# BpodFSM_r2_5.net
KiCad netlist of a schematic drawn in EAGLE
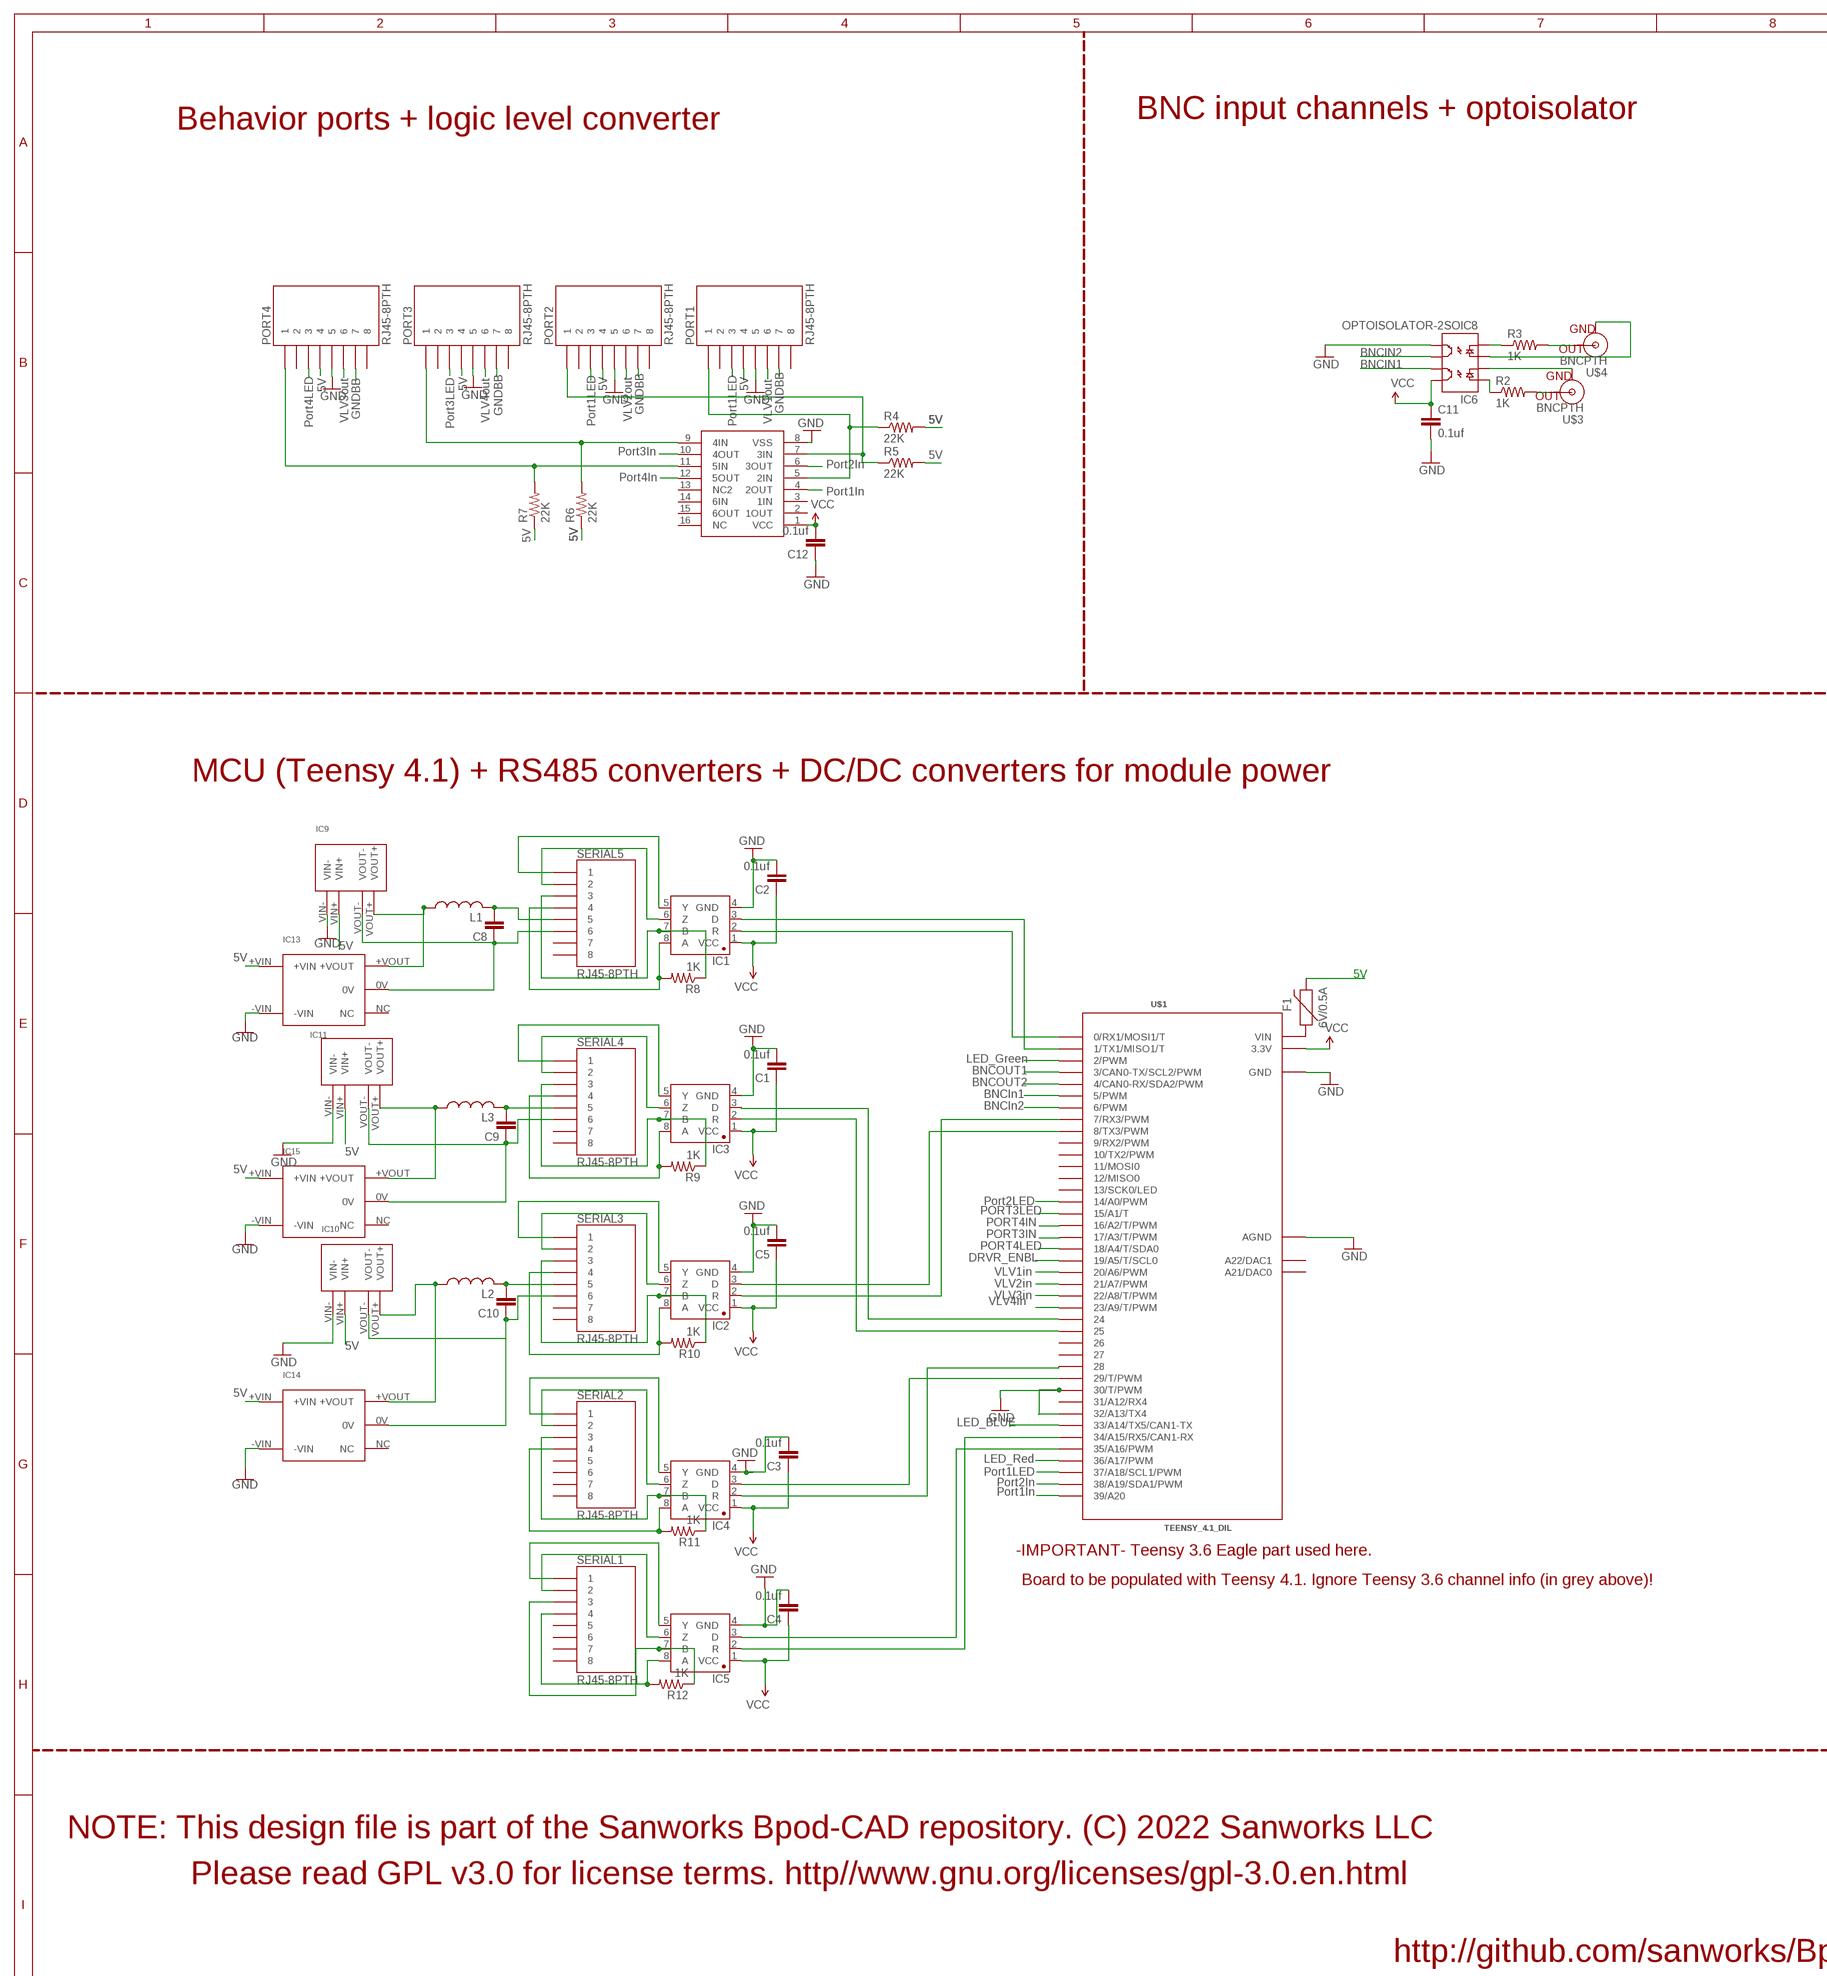
[diagram p0: schematic, sheet 1, part 1 of 2]
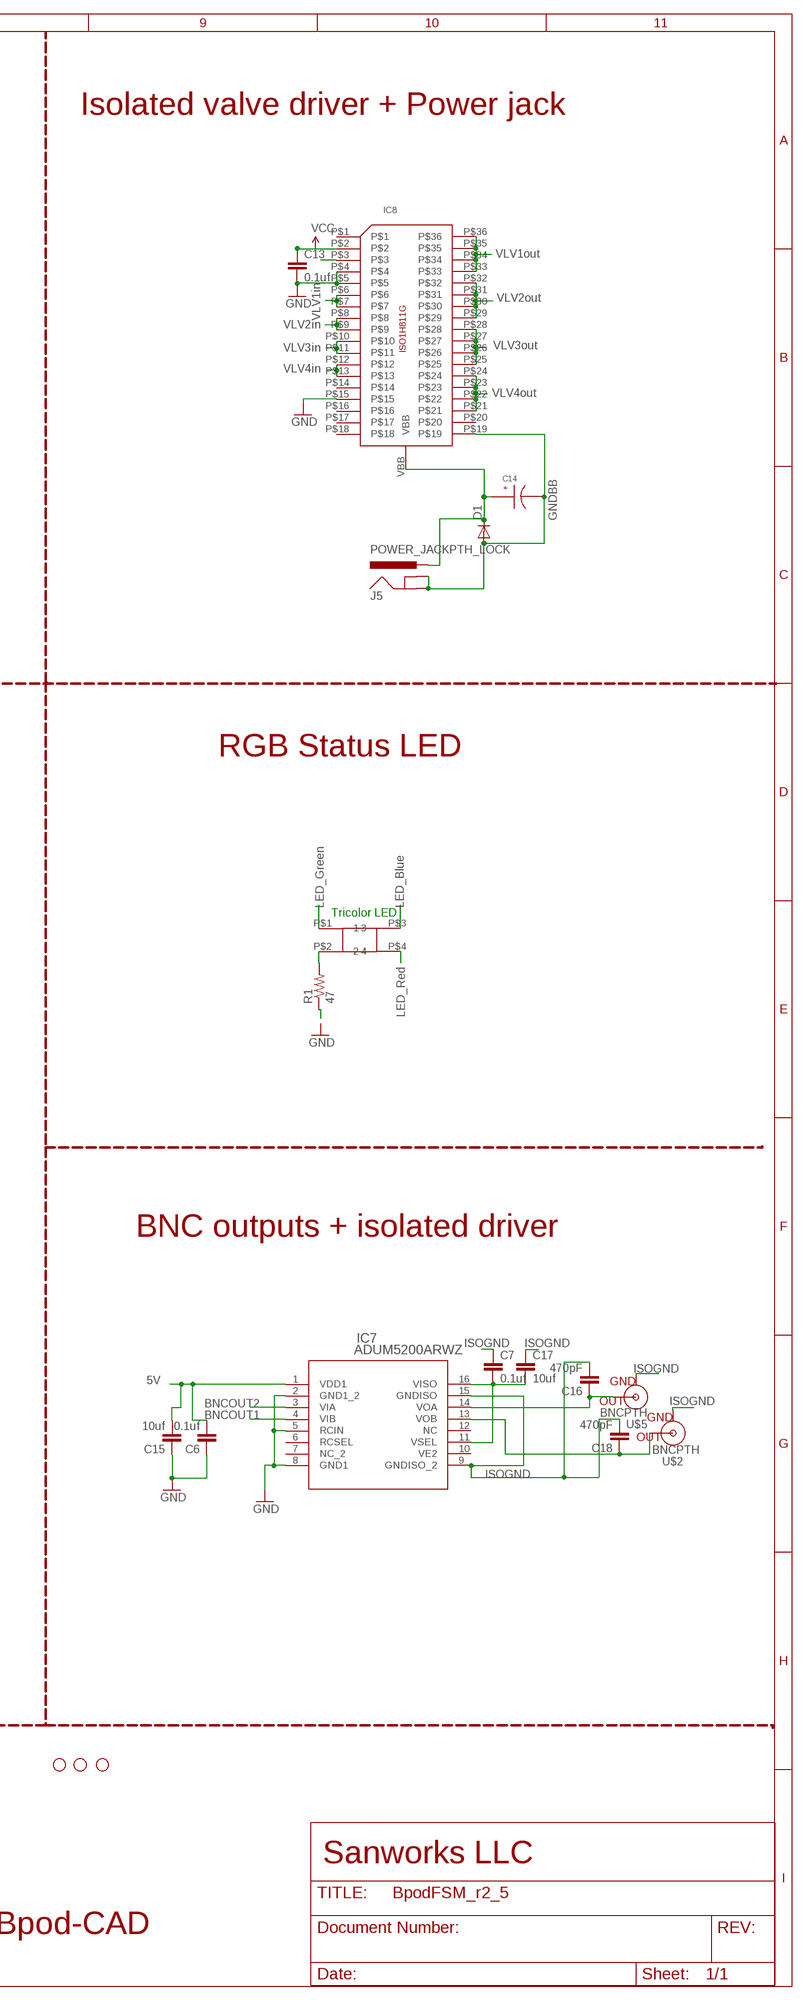
[diagram p1: schematic, sheet 1, part 2 of 2]

(export (version "E")
  (design (tool "Eeschema 10.0.6"))
  (components
    (comp (ref "C1")
      (value "0.1uf")
      (footprint "eagle-import:1206@1")
      (libsource (lib "eagle-import") (part "CAP1206"))
    )
    (comp (ref "C2")
      (value "0.1uf")
      (footprint "eagle-import:1206@1")
      (libsource (lib "eagle-import") (part "CAP1206"))
    )
    (comp (ref "C3")
      (value "0.1uf")
      (footprint "eagle-import:1206@1")
      (libsource (lib "eagle-import") (part "CAP1206"))
    )
    (comp (ref "C4")
      (value "0.1uf")
      (footprint "eagle-import:1206@1")
      (libsource (lib "eagle-import") (part "CAP1206"))
    )
    (comp (ref "C5")
      (value "0.1uf")
      (footprint "eagle-import:1206@1")
      (libsource (lib "eagle-import") (part "CAP1206"))
    )
    (comp (ref "C6")
      (value "0.1uf")
      (footprint "eagle-import:0805")
      (libsource (lib "eagle-import") (part "1.0UF-0805-25V-10%"))
    )
    (comp (ref "C7")
      (value "0.1uf")
      (footprint "eagle-import:0805")
      (libsource (lib "eagle-import") (part "1.0UF-0805-25V-10%"))
    )
    (comp (ref "C8")
      (value "CAP1206")
      (footprint "eagle-import:1206@1")
      (libsource (lib "eagle-import") (part "CAP1206"))
    )
    (comp (ref "C9")
      (value "CAP1206")
      (footprint "eagle-import:1206@1")
      (libsource (lib "eagle-import") (part "CAP1206"))
    )
    (comp (ref "C10")
      (value "CAP1206")
      (footprint "eagle-import:1206@1")
      (libsource (lib "eagle-import") (part "CAP1206"))
    )
    (comp (ref "C11")
      (value "0.1uf")
      (footprint "eagle-import:1206@1")
      (libsource (lib "eagle-import") (part "CAP1206"))
    )
    (comp (ref "C12")
      (value "0.1uf")
      (footprint "eagle-import:1206@1")
      (libsource (lib "eagle-import") (part "CAP1206"))
    )
    (comp (ref "C13")
      (value "0.1uf")
      (footprint "eagle-import:1206@1")
      (libsource (lib "eagle-import") (part "CAP1206"))
    )
    (comp (ref "C14")
      (value "EEE-FK1H100UR")
      (footprint "eagle-import:EEE-FK1H100UR")
      (libsource (lib "eagle-import") (part "EEE-FK1H100UR"))
    )
    (comp (ref "C15")
      (value "10uf")
      (footprint "eagle-import:1206@1")
      (libsource (lib "eagle-import") (part "CAP1206"))
    )
    (comp (ref "C16")
      (value "470pF")
      (footprint "eagle-import:0805")
      (libsource (lib "eagle-import") (part "1.0UF-0805-25V-10%"))
    )
    (comp (ref "C17")
      (value "10uf")
      (footprint "eagle-import:1206@1")
      (libsource (lib "eagle-import") (part "CAP1206"))
    )
    (comp (ref "C18")
      (value "470pF")
      (footprint "eagle-import:0805")
      (libsource (lib "eagle-import") (part "1.0UF-0805-25V-10%"))
    )
    (comp (ref "D1")
      (value "DIODE-DO214AA")
      (footprint "eagle-import:DO214AA")
      (libsource (lib "eagle-import") (part "DIODE-DO214AA"))
    )
    (comp (ref "F1")
      (value "6V/0.5A")
      (footprint "eagle-import:1206")
      (libsource (lib "eagle-import") (part "PPTC_HALF-AMP"))
    )
    (comp (ref "IC1")
      (value "SN65HVD31DR")
      (footprint "eagle-import:SO08")
      (libsource (lib "eagle-import") (part "SN65HVD31DR"))
    )
    (comp (ref "IC2")
      (value "SN65HVD31DR")
      (footprint "eagle-import:SO08")
      (libsource (lib "eagle-import") (part "SN65HVD31DR"))
    )
    (comp (ref "IC3")
      (value "SN65HVD31DR")
      (footprint "eagle-import:SO08")
      (libsource (lib "eagle-import") (part "SN65HVD31DR"))
    )
    (comp (ref "IC4")
      (value "SN65HVD31DR")
      (footprint "eagle-import:SO08")
      (libsource (lib "eagle-import") (part "SN65HVD31DR"))
    )
    (comp (ref "IC5")
      (value "SN65HVD31DR")
      (footprint "eagle-import:SO08")
      (libsource (lib "eagle-import") (part "SN65HVD31DR"))
    )
    (comp (ref "IC6")
      (value "OPTOISOLATOR-2SOIC8")
      (footprint "eagle-import:SO08-2")
      (libsource (lib "eagle-import") (part "OPTOISOLATOR-2SOIC8"))
    )
    (comp (ref "IC7")
      (value "ADUM5200ARWZ")
      (footprint "eagle-import:RW_16")
      (libsource (lib "eagle-import") (part "ADUM5200ARWZ"))
    )
    (comp (ref "IC8")
      (value "ISO1H811G")
      (footprint "eagle-import:ISO1H811G")
      (libsource (lib "eagle-import") (part "ISO1H811G"))
    )
    (comp (ref "IC9")
      (value "NME0509SC")
      (footprint "eagle-import:NME0509SC")
      (libsource (lib "eagle-import") (part "NME0509SC"))
    )
    (comp (ref "IC10")
      (value "NME0509SC")
      (footprint "eagle-import:NME0509SC")
      (libsource (lib "eagle-import") (part "NME0509SC"))
    )
    (comp (ref "IC11")
      (value "NME0509SC")
      (footprint "eagle-import:NME0509SC")
      (libsource (lib "eagle-import") (part "NME0509SC"))
    )
    (comp (ref "IC12")
      (value "CD4050")
      (footprint "eagle-import:SO16")
      (libsource (lib "eagle-import") (part "CD4050"))
    )
    (comp (ref "IC13")
      (value "MTU1D0505MC")
      (footprint "eagle-import:MTU1D0505MC")
      (libsource (lib "eagle-import") (part "MTU1D0505MC"))
    )
    (comp (ref "IC14")
      (value "MTU1D0505MC")
      (footprint "eagle-import:MTU1D0505MC")
      (libsource (lib "eagle-import") (part "MTU1D0505MC"))
    )
    (comp (ref "IC15")
      (value "MTU1D0505MC")
      (footprint "eagle-import:MTU1D0505MC")
      (libsource (lib "eagle-import") (part "MTU1D0505MC"))
    )
    (comp (ref "J5")
      (value "POWER_JACKPTH_LOCK")
      (footprint "eagle-import:POWER_JACK_PTH_LOCK")
      (libsource (lib "eagle-import") (part "POWER_JACKPTH_LOCK"))
    )
    (comp (ref "JP3")
      (value "STAND-OFF")
      (footprint "eagle-import:STAND-OFF")
      (libsource (lib "eagle-import") (part "STAND-OFF"))
    )
    (comp (ref "JP4")
      (value "STAND-OFF")
      (footprint "eagle-import:STAND-OFF")
      (libsource (lib "eagle-import") (part "STAND-OFF"))
    )
    (comp (ref "JP5")
      (value "STAND-OFF")
      (footprint "eagle-import:STAND-OFF")
      (libsource (lib "eagle-import") (part "STAND-OFF"))
    )
    (comp (ref "L1")
      (value "L-USL3225M")
      (footprint "eagle-import:L3225M")
      (libsource (lib "eagle-import") (part "L-USL3225M"))
    )
    (comp (ref "L2")
      (value "L-USL3225M")
      (footprint "eagle-import:L3225M")
      (libsource (lib "eagle-import") (part "L-USL3225M"))
    )
    (comp (ref "L3")
      (value "L-USL3225M")
      (footprint "eagle-import:L3225M")
      (libsource (lib "eagle-import") (part "L-USL3225M"))
    )
    (comp (ref "PORT1")
      (value "RJ45-8PTH")
      (footprint "eagle-import:RJ45-8")
      (libsource (lib "eagle-import") (part "RJ45-8PTH"))
    )
    (comp (ref "PORT2")
      (value "RJ45-8PTH")
      (footprint "eagle-import:RJ45-8")
      (libsource (lib "eagle-import") (part "RJ45-8PTH"))
    )
    (comp (ref "PORT3")
      (value "RJ45-8PTH")
      (footprint "eagle-import:RJ45-8")
      (libsource (lib "eagle-import") (part "RJ45-8PTH"))
    )
    (comp (ref "PORT4")
      (value "RJ45-8PTH")
      (footprint "eagle-import:RJ45-8")
      (libsource (lib "eagle-import") (part "RJ45-8PTH"))
    )
    (comp (ref "R1")
      (value "47")
      (footprint "eagle-import:1206")
      (libsource (lib "eagle-import") (part "RESISTOR1206"))
    )
    (comp (ref "R2")
      (value "1K")
      (footprint "eagle-import:1206")
      (libsource (lib "eagle-import") (part "SparkFun-Resistors_RESISTOR1206"))
    )
    (comp (ref "R3")
      (value "1K")
      (footprint "eagle-import:1206")
      (libsource (lib "eagle-import") (part "SparkFun-Resistors_RESISTOR1206"))
    )
    (comp (ref "R4")
      (value "22K")
      (footprint "eagle-import:1206")
      (libsource (lib "eagle-import") (part "SparkFun-Resistors_RESISTOR1206"))
    )
    (comp (ref "R5")
      (value "22K")
      (footprint "eagle-import:1206")
      (libsource (lib "eagle-import") (part "SparkFun-Resistors_RESISTOR1206"))
    )
    (comp (ref "R6")
      (value "22K")
      (footprint "eagle-import:1206")
      (libsource (lib "eagle-import") (part "SparkFun-Resistors_RESISTOR1206"))
    )
    (comp (ref "R7")
      (value "22K")
      (footprint "eagle-import:1206")
      (libsource (lib "eagle-import") (part "SparkFun-Resistors_RESISTOR1206"))
    )
    (comp (ref "R8")
      (value "1K")
      (footprint "eagle-import:1206")
      (libsource (lib "eagle-import") (part "SparkFun-Resistors_RESISTOR1206"))
    )
    (comp (ref "R9")
      (value "1K")
      (footprint "eagle-import:1206")
      (libsource (lib "eagle-import") (part "SparkFun-Resistors_RESISTOR1206"))
    )
    (comp (ref "R10")
      (value "1K")
      (footprint "eagle-import:1206")
      (libsource (lib "eagle-import") (part "SparkFun-Resistors_RESISTOR1206"))
    )
    (comp (ref "R11")
      (value "1K")
      (footprint "eagle-import:1206")
      (libsource (lib "eagle-import") (part "SparkFun-Resistors_RESISTOR1206"))
    )
    (comp (ref "R12")
      (value "1K")
      (footprint "eagle-import:1206")
      (libsource (lib "eagle-import") (part "SparkFun-Resistors_RESISTOR1206"))
    )
    (comp (ref "SERIAL1")
      (value "RJ45-8PTH")
      (footprint "eagle-import:RJ45-8")
      (libsource (lib "eagle-import") (part "RJ45-8PTH"))
    )
    (comp (ref "SERIAL2")
      (value "RJ45-8PTH")
      (footprint "eagle-import:RJ45-8")
      (libsource (lib "eagle-import") (part "RJ45-8PTH"))
    )
    (comp (ref "SERIAL3")
      (value "RJ45-8PTH")
      (footprint "eagle-import:RJ45-8")
      (libsource (lib "eagle-import") (part "RJ45-8PTH"))
    )
    (comp (ref "SERIAL4")
      (value "RJ45-8PTH")
      (footprint "eagle-import:RJ45-8")
      (libsource (lib "eagle-import") (part "RJ45-8PTH"))
    )
    (comp (ref "SERIAL5")
      (value "RJ45-8PTH")
      (footprint "eagle-import:RJ45-8")
      (libsource (lib "eagle-import") (part "RJ45-8PTH"))
    )
    (comp (ref "U$1")
      (value "TEENSY_4.1_DIL")
      (footprint "eagle-import:TEENSY_3.6_DIL")
      (libsource (lib "eagle-import") (part "TEENSY_3.6_DIL"))
    )
    (comp (ref "U$2")
      (value "BNCPTH")
      (footprint "eagle-import:BNC")
      (libsource (lib "eagle-import") (part "BNCPTH"))
    )
    (comp (ref "U$3")
      (value "BNCPTH")
      (footprint "eagle-import:BNC")
      (libsource (lib "eagle-import") (part "BNCPTH"))
    )
    (comp (ref "U$4")
      (value "BNCPTH")
      (footprint "eagle-import:BNC")
      (libsource (lib "eagle-import") (part "BNCPTH"))
    )
    (comp (ref "U$5")
      (value "BNCPTH")
      (footprint "eagle-import:BNC")
      (libsource (lib "eagle-import") (part "BNCPTH"))
    )
    (comp (ref "U$8")
      (value "SQUARE_TRICOLOR_LED")
      (footprint "eagle-import:SQUARE_TRICOLOR_LED")
      (libsource (lib "eagle-import") (part "SQUARE_TRICOLOR_LED"))
    )
  )
  (nets
    (net (code "1") (name "/5V") (class "Default")
      (node (ref "C15") (pin "2") (pinfunction "2_2") (pintype "passive"))
      (node (ref "C6") (pin "2") (pinfunction "2_2") (pintype "passive"))
      (node (ref "F1") (pin "2") (pinfunction "2_2") (pintype "bidirectional"))
      (node (ref "IC10") (pin "VIN+") (pinfunction "VIN+_VIN+") (pintype "bidirectional"))
      (node (ref "IC11") (pin "VIN+") (pinfunction "VIN+_VIN+") (pintype "bidirectional"))
      (node (ref "IC13") (pin "+VIN") (pinfunction "+VIN_+VIN") (pintype "bidirectional"))
      (node (ref "IC14") (pin "+VIN") (pinfunction "+VIN_+VIN") (pintype "bidirectional"))
      (node (ref "IC15") (pin "+VIN") (pinfunction "+VIN_+VIN") (pintype "bidirectional"))
      (node (ref "IC7") (pin "1") (pinfunction "VDD1_1") (pintype "passive"))
      (node (ref "IC9") (pin "VIN+") (pinfunction "VIN+_VIN+") (pintype "bidirectional"))
      (node (ref "PORT1") (pin "4") (pinfunction "4_4") (pintype "bidirectional"))
      (node (ref "PORT2") (pin "4") (pinfunction "4_4") (pintype "bidirectional"))
      (node (ref "PORT3") (pin "4") (pinfunction "4_4") (pintype "bidirectional"))
      (node (ref "PORT4") (pin "4") (pinfunction "4_4") (pintype "bidirectional"))
      (node (ref "R4") (pin "2") (pinfunction "2_2") (pintype "passive"))
      (node (ref "R5") (pin "2") (pinfunction "2_2") (pintype "passive"))
      (node (ref "R6") (pin "1") (pinfunction "1_1") (pintype "passive"))
      (node (ref "R7") (pin "1") (pinfunction "1_1") (pintype "passive"))
    )
    (net (code "2") (name "/BNCIN1") (class "Default")
      (node (ref "IC6") (pin "7") (pinfunction "EM1_7") (pintype "bidirectional"))
      (node (ref "U$1") (pin "6") (pinfunction "6/PWM_6") (pintype "bidirectional"))
    )
    (net (code "3") (name "/BNCIN2") (class "Default")
      (node (ref "IC6") (pin "6") (pinfunction "CL2_6") (pintype "bidirectional"))
      (node (ref "U$1") (pin "5") (pinfunction "5/PWM_5") (pintype "bidirectional"))
    )
    (net (code "4") (name "/BNCOUT1") (class "Default")
      (node (ref "IC7") (pin "4") (pinfunction "VIB_4") (pintype "passive"))
      (node (ref "U$1") (pin "4") (pinfunction "4/CAN0-RX/SDA2/PWM_4") (pintype "bidirectional"))
    )
    (net (code "5") (name "/BNCOUT2") (class "Default")
      (node (ref "IC7") (pin "3") (pinfunction "VIA_3") (pintype "passive"))
      (node (ref "U$1") (pin "3") (pinfunction "3/CAN0-TX/SCL2/PWM_3") (pintype "bidirectional"))
    )
    (net (code "6") (name "/DRVR_ENBL") (class "Default")
      (node (ref "IC8") (pin "P$3") (pinfunction "P$3_P$3") (pintype "bidirectional"))
      (node (ref "U$1") (pin "19/A5") (pinfunction "19/A5/T/SCL0_19/A5") (pintype "bidirectional"))
    )
    (net (code "7") (name "/GNDBB") (class "Default")
      (node (ref "C14") (pin "CATHODE") (pinfunction "CATHODE_CATHODE") (pintype "bidirectional"))
      (node (ref "D1") (pin "A") (pinfunction "A_A") (pintype "passive"))
      (node (ref "IC8") (pin "P$19") (pinfunction "P$19_P$19") (pintype "bidirectional"))
      (node (ref "J5") (pin "GND") (pinfunction "GND_GND") (pintype "bidirectional"))
      (node (ref "J5") (pin "GNDBREAK") (pinfunction "GNDBREAK_GNDBREAK") (pintype "bidirectional"))
      (node (ref "PORT1") (pin "7") (pinfunction "7_7") (pintype "bidirectional"))
      (node (ref "PORT2") (pin "7") (pinfunction "7_7") (pintype "bidirectional"))
      (node (ref "PORT3") (pin "7") (pinfunction "7_7") (pintype "bidirectional"))
      (node (ref "PORT4") (pin "7") (pinfunction "7_7") (pintype "bidirectional"))
    )
    (net (code "8") (name "/ISOGND") (class "Default")
      (node (ref "C16") (pin "2") (pinfunction "2_2") (pintype "passive"))
      (node (ref "C17") (pin "1") (pinfunction "1_1") (pintype "passive"))
      (node (ref "C18") (pin "2") (pinfunction "2_2") (pintype "passive"))
      (node (ref "C7") (pin "1") (pinfunction "1_1") (pintype "passive"))
      (node (ref "IC7") (pin "15") (pinfunction "GNDISO_15") (pintype "passive"))
      (node (ref "IC7") (pin "9") (pinfunction "GNDISO_2_9") (pintype "passive"))
      (node (ref "U$2") (pin "GND") (pinfunction "GND_GND") (pintype "bidirectional"))
      (node (ref "U$5") (pin "GND") (pinfunction "GND_GND") (pintype "bidirectional"))
    )
    (net (code "9") (name "/LED_BLUE") (class "Default")
      (node (ref "U$1") (pin "33/A14") (pinfunction "33/A14/TX5/CAN1-TX_33/A14") (pintype "bidirectional"))
      (node (ref "U$8") (pin "P$3") (pinfunction "3_P$3") (pintype "bidirectional"))
    )
    (net (code "10") (name "/LED_GREEN") (class "Default")
      (node (ref "U$1") (pin "2") (pinfunction "2/PWM_2") (pintype "bidirectional"))
      (node (ref "U$8") (pin "P$1") (pinfunction "1_P$1") (pintype "bidirectional"))
    )
    (net (code "11") (name "/LED_RED") (class "Default")
      (node (ref "U$1") (pin "36/A17") (pinfunction "36/A17/PWM_36/A17") (pintype "bidirectional"))
      (node (ref "U$8") (pin "P$4") (pinfunction "4_P$4") (pintype "bidirectional"))
    )
    (net (code "12") (name "/PORT1IN") (class "Default")
      (node (ref "IC12") (pin "4") (pinfunction "2OUT_4") (pintype "bidirectional"))
      (node (ref "U$1") (pin "39/A20") (pinfunction "39/A20_39/A20") (pintype "bidirectional"))
    )
    (net (code "13") (name "/PORT1LED") (class "Default")
      (node (ref "PORT1") (pin "3") (pinfunction "3_3") (pintype "bidirectional"))
      (node (ref "U$1") (pin "37/A18") (pinfunction "37/A18/SCL1/PWM_37/A18") (pintype "bidirectional"))
    )
    (net (code "14") (name "/PORT2IN") (class "Default")
      (node (ref "IC12") (pin "6") (pinfunction "3OUT_6") (pintype "bidirectional"))
      (node (ref "U$1") (pin "38/A19") (pinfunction "38/A19/SDA1/PWM_38/A19") (pintype "bidirectional"))
    )
    (net (code "15") (name "/PORT2LED") (class "Default")
      (node (ref "PORT2") (pin "3") (pinfunction "3_3") (pintype "bidirectional"))
      (node (ref "U$1") (pin "14/A0") (pinfunction "14/A0/PWM_14/A0") (pintype "bidirectional"))
    )
    (net (code "16") (name "/PORT3IN") (class "Default")
      (node (ref "IC12") (pin "10") (pinfunction "4OUT_10") (pintype "bidirectional"))
      (node (ref "U$1") (pin "17/A3") (pinfunction "17/A3/T/PWM_17/A3") (pintype "bidirectional"))
    )
    (net (code "17") (name "/PORT3LED") (class "Default")
      (node (ref "PORT3") (pin "3") (pinfunction "3_3") (pintype "bidirectional"))
      (node (ref "U$1") (pin "15/A1") (pinfunction "15/A1/T_15/A1") (pintype "bidirectional"))
    )
    (net (code "18") (name "/PORT4IN") (class "Default")
      (node (ref "IC12") (pin "12") (pinfunction "5OUT_12") (pintype "bidirectional"))
      (node (ref "U$1") (pin "16/A2") (pinfunction "16/A2/T/PWM_16/A2") (pintype "bidirectional"))
    )
    (net (code "19") (name "/PORT4LED") (class "Default")
      (node (ref "PORT4") (pin "3") (pinfunction "3_3") (pintype "bidirectional"))
      (node (ref "U$1") (pin "18/A4") (pinfunction "18/A4/T/SDA0_18/A4") (pintype "bidirectional"))
    )
    (net (code "20") (name "/VLV1IN") (class "Default")
      (node (ref "IC8") (pin "P$6") (pinfunction "P$6_P$6") (pintype "bidirectional"))
      (node (ref "IC8") (pin "P$7") (pinfunction "P$7_P$7") (pintype "bidirectional"))
      (node (ref "U$1") (pin "23/A9") (pinfunction "23/A9/T/PWM_23/A9") (pintype "bidirectional"))
    )
    (net (code "21") (name "/VLV1OUT") (class "Default")
      (node (ref "IC8") (pin "P$33") (pinfunction "P$33_P$33") (pintype "bidirectional"))
      (node (ref "IC8") (pin "P$34") (pinfunction "P$34_P$34") (pintype "bidirectional"))
      (node (ref "IC8") (pin "P$35") (pinfunction "P$35_P$35") (pintype "bidirectional"))
      (node (ref "IC8") (pin "P$36") (pinfunction "P$36_P$36") (pintype "bidirectional"))
      (node (ref "PORT1") (pin "6") (pinfunction "6_6") (pintype "bidirectional"))
    )
    (net (code "22") (name "/VLV2IN") (class "Default")
      (node (ref "IC8") (pin "P$8") (pinfunction "P$8_P$8") (pintype "bidirectional"))
      (node (ref "IC8") (pin "P$9") (pinfunction "P$9_P$9") (pintype "bidirectional"))
      (node (ref "U$1") (pin "22/A8") (pinfunction "22/A8/T/PWM_22/A8") (pintype "bidirectional"))
    )
    (net (code "23") (name "/VLV2OUT") (class "Default")
      (node (ref "IC8") (pin "P$29") (pinfunction "P$29_P$29") (pintype "bidirectional"))
      (node (ref "IC8") (pin "P$30") (pinfunction "P$30_P$30") (pintype "bidirectional"))
      (node (ref "IC8") (pin "P$31") (pinfunction "P$31_P$31") (pintype "bidirectional"))
      (node (ref "IC8") (pin "P$32") (pinfunction "P$32_P$32") (pintype "bidirectional"))
      (node (ref "PORT2") (pin "6") (pinfunction "6_6") (pintype "bidirectional"))
    )
    (net (code "24") (name "/VLV3IN") (class "Default")
      (node (ref "IC8") (pin "P$12") (pinfunction "P$12_P$12") (pintype "bidirectional"))
      (node (ref "IC8") (pin "P$13") (pinfunction "P$13_P$13") (pintype "bidirectional"))
      (node (ref "U$1") (pin "20/A6") (pinfunction "20/A6/PWM_20/A6") (pintype "bidirectional"))
    )
    (net (code "25") (name "/VLV3OUT") (class "Default")
      (node (ref "IC8") (pin "P$21") (pinfunction "P$21_P$21") (pintype "bidirectional"))
      (node (ref "IC8") (pin "P$22") (pinfunction "P$22_P$22") (pintype "bidirectional"))
      (node (ref "IC8") (pin "P$23") (pinfunction "P$23_P$23") (pintype "bidirectional"))
      (node (ref "IC8") (pin "P$24") (pinfunction "P$24_P$24") (pintype "bidirectional"))
      (node (ref "PORT3") (pin "6") (pinfunction "6_6") (pintype "bidirectional"))
    )
    (net (code "26") (name "/VLV4IN") (class "Default")
      (node (ref "IC8") (pin "P$10") (pinfunction "P$10_P$10") (pintype "bidirectional"))
      (node (ref "IC8") (pin "P$11") (pinfunction "P$11_P$11") (pintype "bidirectional"))
      (node (ref "U$1") (pin "21/A7") (pinfunction "21/A7/PWM_21/A7") (pintype "bidirectional"))
    )
    (net (code "27") (name "/VLV4OUT") (class "Default")
      (node (ref "IC8") (pin "P$25") (pinfunction "P$25_P$25") (pintype "bidirectional"))
      (node (ref "IC8") (pin "P$26") (pinfunction "P$26_P$26") (pintype "bidirectional"))
      (node (ref "IC8") (pin "P$27") (pinfunction "P$27_P$27") (pintype "bidirectional"))
      (node (ref "IC8") (pin "P$28") (pinfunction "P$28_P$28") (pintype "bidirectional"))
      (node (ref "PORT4") (pin "6") (pinfunction "6_6") (pintype "bidirectional"))
    )
    (net (code "28") (name "GND") (class "Default")
      (node (ref "C1") (pin "2") (pinfunction "2_2") (pintype "passive"))
      (node (ref "C11") (pin "2") (pinfunction "2_2") (pintype "passive"))
      (node (ref "C12") (pin "1") (pinfunction "1_1") (pintype "passive"))
      (node (ref "C13") (pin "2") (pinfunction "2_2") (pintype "passive"))
      (node (ref "C15") (pin "1") (pinfunction "1_1") (pintype "passive"))
      (node (ref "C2") (pin "2") (pinfunction "2_2") (pintype "passive"))
      (node (ref "C3") (pin "2") (pinfunction "2_2") (pintype "passive"))
      (node (ref "C4") (pin "2") (pinfunction "2_2") (pintype "passive"))
      (node (ref "C5") (pin "2") (pinfunction "2_2") (pintype "passive"))
      (node (ref "C6") (pin "1") (pinfunction "1_1") (pintype "passive"))
      (node (ref "IC1") (pin "4") (pinfunction "GND_4") (pintype "bidirectional"))
      (node (ref "IC10") (pin "VIN-") (pinfunction "VIN-_VIN-") (pintype "bidirectional"))
      (node (ref "IC11") (pin "VIN-") (pinfunction "VIN-_VIN-") (pintype "bidirectional"))
      (node (ref "IC12") (pin "8") (pinfunction "VSS_8") (pintype "bidirectional"))
      (node (ref "IC13") (pin "-VIN") (pinfunction "-VIN_-VIN") (pintype "bidirectional"))
      (node (ref "IC14") (pin "-VIN") (pinfunction "-VIN_-VIN") (pintype "bidirectional"))
      (node (ref "IC15") (pin "-VIN") (pinfunction "-VIN_-VIN") (pintype "bidirectional"))
      (node (ref "IC2") (pin "4") (pinfunction "GND_4") (pintype "bidirectional"))
      (node (ref "IC3") (pin "4") (pinfunction "GND_4") (pintype "bidirectional"))
      (node (ref "IC4") (pin "4") (pinfunction "GND_4") (pintype "bidirectional"))
      (node (ref "IC5") (pin "4") (pinfunction "GND_4") (pintype "bidirectional"))
      (node (ref "IC6") (pin "5") (pinfunction "EM2_5") (pintype "bidirectional"))
      (node (ref "IC7") (pin "2") (pinfunction "GND1_2_2") (pintype "passive"))
      (node (ref "IC7") (pin "5") (pinfunction "RCIN_5") (pintype "passive"))
      (node (ref "IC7") (pin "8") (pinfunction "GND1_8") (pintype "passive"))
      (node (ref "IC8") (pin "P$15") (pinfunction "P$15_P$15") (pintype "bidirectional"))
      (node (ref "IC8") (pin "P$4") (pinfunction "P$4_P$4") (pintype "bidirectional"))
      (node (ref "IC8") (pin "P$5") (pinfunction "P$5_P$5") (pintype "bidirectional"))
      (node (ref "IC9") (pin "VIN-") (pinfunction "VIN-_VIN-") (pintype "bidirectional"))
      (node (ref "PORT1") (pin "5") (pinfunction "5_5") (pintype "bidirectional"))
      (node (ref "PORT2") (pin "5") (pinfunction "5_5") (pintype "bidirectional"))
      (node (ref "PORT3") (pin "5") (pinfunction "5_5") (pintype "bidirectional"))
      (node (ref "PORT4") (pin "5") (pinfunction "5_5") (pintype "bidirectional"))
      (node (ref "R1") (pin "1") (pinfunction "1_1") (pintype "passive"))
      (node (ref "U$1") (pin "30") (pinfunction "30/T/PWM_30") (pintype "bidirectional"))
      (node (ref "U$1") (pin "32/A13") (pinfunction "32/A13/TX4_32/A13") (pintype "bidirectional"))
      (node (ref "U$1") (pin "AGND") (pinfunction "AGND_AGND") (pintype "power_in"))
      (node (ref "U$1") (pin "GND") (pinfunction "GND_GND") (pintype "power_in"))
      (node (ref "U$1") (pin "GND1") (pinfunction "GND_GND1") (pintype "power_in"))
    )
    (net (code "29") (name "Net-(C8-Pad1)") (class "Default")
      (node (ref "C8") (pin "1") (pinfunction "1_1") (pintype "passive"))
      (node (ref "IC13") (pin "0V") (pinfunction "0V_0V") (pintype "bidirectional"))
      (node (ref "IC9") (pin "VOUT-") (pinfunction "VOUT-_VOUT-") (pintype "bidirectional"))
      (node (ref "SERIAL5") (pin "6") (pinfunction "6_6") (pintype "bidirectional"))
    )
    (net (code "30") (name "Net-(C8-Pad2)") (class "Default")
      (node (ref "C8") (pin "2") (pinfunction "2_2") (pintype "passive"))
      (node (ref "L1") (pin "2") (pinfunction "2_2") (pintype "passive"))
      (node (ref "SERIAL5") (pin "5") (pinfunction "5_5") (pintype "bidirectional"))
    )
    (net (code "31") (name "Net-(C9-Pad1)") (class "Default")
      (node (ref "C9") (pin "1") (pinfunction "1_1") (pintype "passive"))
      (node (ref "IC11") (pin "VOUT-") (pinfunction "VOUT-_VOUT-") (pintype "bidirectional"))
      (node (ref "IC15") (pin "0V") (pinfunction "0V_0V") (pintype "bidirectional"))
      (node (ref "SERIAL4") (pin "6") (pinfunction "6_6") (pintype "bidirectional"))
    )
    (net (code "32") (name "Net-(C9-Pad2)") (class "Default")
      (node (ref "C9") (pin "2") (pinfunction "2_2") (pintype "passive"))
      (node (ref "L3") (pin "2") (pinfunction "2_2") (pintype "passive"))
      (node (ref "SERIAL4") (pin "5") (pinfunction "5_5") (pintype "bidirectional"))
    )
    (net (code "33") (name "Net-(C10-Pad1)") (class "Default")
      (node (ref "C10") (pin "1") (pinfunction "1_1") (pintype "passive"))
      (node (ref "IC10") (pin "VOUT-") (pinfunction "VOUT-_VOUT-") (pintype "bidirectional"))
      (node (ref "IC14") (pin "0V") (pinfunction "0V_0V") (pintype "bidirectional"))
      (node (ref "SERIAL3") (pin "6") (pinfunction "6_6") (pintype "bidirectional"))
    )
    (net (code "34") (name "Net-(C10-Pad2)") (class "Default")
      (node (ref "C10") (pin "2") (pinfunction "2_2") (pintype "passive"))
      (node (ref "L2") (pin "2") (pinfunction "2_2") (pintype "passive"))
      (node (ref "SERIAL3") (pin "5") (pinfunction "5_5") (pintype "bidirectional"))
    )
    (net (code "35") (name "Net-(C14-PadANODE)") (class "Default")
      (node (ref "C14") (pin "ANODE") (pinfunction "ANODE_ANODE") (pintype "bidirectional"))
      (node (ref "D1") (pin "C") (pinfunction "C_C") (pintype "passive"))
      (node (ref "IC8") (pin "VBB") (pinfunction "VBB_VBB") (pintype "bidirectional"))
      (node (ref "J5") (pin "PWR") (pinfunction "PWR_PWR") (pintype "bidirectional"))
    )
    (net (code "36") (name "Net-(F1-Pad1)") (class "Default")
      (node (ref "F1") (pin "1") (pinfunction "1_1") (pintype "bidirectional"))
      (node (ref "U$1") (pin "VIN") (pinfunction "VIN_VIN") (pintype "power_in"))
    )
    (net (code "37") (name "Net-(IC1-A)") (class "Default")
      (node (ref "IC1") (pin "8") (pinfunction "A_8") (pintype "bidirectional"))
      (node (ref "R8") (pin "2") (pinfunction "2_2") (pintype "passive"))
      (node (ref "SERIAL5") (pin "4") (pinfunction "4_4") (pintype "bidirectional"))
    )
    (net (code "38") (name "Net-(IC1-B)") (class "Default")
      (node (ref "IC1") (pin "7") (pinfunction "B_7") (pintype "bidirectional"))
      (node (ref "R8") (pin "1") (pinfunction "1_1") (pintype "passive"))
      (node (ref "SERIAL5") (pin "3") (pinfunction "3_3") (pintype "bidirectional"))
    )
    (net (code "39") (name "Net-(IC1-D)") (class "Default")
      (node (ref "IC1") (pin "3") (pinfunction "D_3") (pintype "bidirectional"))
      (node (ref "U$1") (pin "1") (pinfunction "1/TX1/MISO1/T_1") (pintype "bidirectional"))
    )
    (net (code "40") (name "Net-(IC1-R)") (class "Default")
      (node (ref "IC1") (pin "2") (pinfunction "R_2") (pintype "bidirectional"))
      (node (ref "U$1") (pin "0") (pinfunction "0/RX1/MOSI1/T_0") (pintype "bidirectional"))
    )
    (net (code "41") (name "Net-(IC1-Y)") (class "Default")
      (node (ref "IC1") (pin "5") (pinfunction "Y_5") (pintype "bidirectional"))
      (node (ref "SERIAL5") (pin "1") (pinfunction "1_1") (pintype "bidirectional"))
    )
    (net (code "42") (name "Net-(IC1-Z)") (class "Default")
      (node (ref "IC1") (pin "6") (pinfunction "Z_6") (pintype "bidirectional"))
      (node (ref "SERIAL5") (pin "2") (pinfunction "2_2") (pintype "bidirectional"))
    )
    (net (code "43") (name "Net-(IC2-A)") (class "Default")
      (node (ref "IC2") (pin "8") (pinfunction "A_8") (pintype "bidirectional"))
      (node (ref "R10") (pin "2") (pinfunction "2_2") (pintype "passive"))
      (node (ref "SERIAL3") (pin "4") (pinfunction "4_4") (pintype "bidirectional"))
    )
    (net (code "44") (name "Net-(IC2-B)") (class "Default")
      (node (ref "IC2") (pin "7") (pinfunction "B_7") (pintype "bidirectional"))
      (node (ref "R10") (pin "1") (pinfunction "1_1") (pintype "passive"))
      (node (ref "SERIAL3") (pin "3") (pinfunction "3_3") (pintype "bidirectional"))
    )
    (net (code "45") (name "Net-(IC2-D)") (class "Default")
      (node (ref "IC2") (pin "3") (pinfunction "D_3") (pintype "bidirectional"))
      (node (ref "U$1") (pin "8") (pinfunction "8/TX3/PWM_8") (pintype "bidirectional"))
    )
    (net (code "46") (name "Net-(IC2-R)") (class "Default")
      (node (ref "IC2") (pin "2") (pinfunction "R_2") (pintype "bidirectional"))
      (node (ref "U$1") (pin "7") (pinfunction "7/RX3/PWM_7") (pintype "bidirectional"))
    )
    (net (code "47") (name "Net-(IC2-Y)") (class "Default")
      (node (ref "IC2") (pin "5") (pinfunction "Y_5") (pintype "bidirectional"))
      (node (ref "SERIAL3") (pin "1") (pinfunction "1_1") (pintype "bidirectional"))
    )
    (net (code "48") (name "Net-(IC2-Z)") (class "Default")
      (node (ref "IC2") (pin "6") (pinfunction "Z_6") (pintype "bidirectional"))
      (node (ref "SERIAL3") (pin "2") (pinfunction "2_2") (pintype "bidirectional"))
    )
    (net (code "49") (name "Net-(IC3-A)") (class "Default")
      (node (ref "IC3") (pin "8") (pinfunction "A_8") (pintype "bidirectional"))
      (node (ref "R9") (pin "2") (pinfunction "2_2") (pintype "passive"))
      (node (ref "SERIAL4") (pin "4") (pinfunction "4_4") (pintype "bidirectional"))
    )
    (net (code "50") (name "Net-(IC3-B)") (class "Default")
      (node (ref "IC3") (pin "7") (pinfunction "B_7") (pintype "bidirectional"))
      (node (ref "R9") (pin "1") (pinfunction "1_1") (pintype "passive"))
      (node (ref "SERIAL4") (pin "3") (pinfunction "3_3") (pintype "bidirectional"))
    )
    (net (code "51") (name "Net-(IC3-D)") (class "Default")
      (node (ref "IC3") (pin "3") (pinfunction "D_3") (pintype "bidirectional"))
      (node (ref "U$1") (pin "24") (pinfunction "24_24") (pintype "bidirectional"))
    )
    (net (code "52") (name "Net-(IC3-R)") (class "Default")
      (node (ref "IC3") (pin "2") (pinfunction "R_2") (pintype "bidirectional"))
      (node (ref "U$1") (pin "25") (pinfunction "25_25") (pintype "bidirectional"))
    )
    (net (code "53") (name "Net-(IC3-Y)") (class "Default")
      (node (ref "IC3") (pin "5") (pinfunction "Y_5") (pintype "bidirectional"))
      (node (ref "SERIAL4") (pin "1") (pinfunction "1_1") (pintype "bidirectional"))
    )
    (net (code "54") (name "Net-(IC3-Z)") (class "Default")
      (node (ref "IC3") (pin "6") (pinfunction "Z_6") (pintype "bidirectional"))
      (node (ref "SERIAL4") (pin "2") (pinfunction "2_2") (pintype "bidirectional"))
    )
    (net (code "55") (name "Net-(IC4-A)") (class "Default")
      (node (ref "IC4") (pin "8") (pinfunction "A_8") (pintype "bidirectional"))
      (node (ref "R11") (pin "2") (pinfunction "2_2") (pintype "passive"))
      (node (ref "SERIAL2") (pin "4") (pinfunction "4_4") (pintype "bidirectional"))
    )
    (net (code "56") (name "Net-(IC4-B)") (class "Default")
      (node (ref "IC4") (pin "7") (pinfunction "B_7") (pintype "bidirectional"))
      (node (ref "R11") (pin "1") (pinfunction "1_1") (pintype "passive"))
      (node (ref "SERIAL2") (pin "3") (pinfunction "3_3") (pintype "bidirectional"))
    )
    (net (code "57") (name "Net-(IC4-D)") (class "Default")
      (node (ref "IC4") (pin "3") (pinfunction "D_3") (pintype "bidirectional"))
      (node (ref "U$1") (pin "29") (pinfunction "29/T/PWM_29") (pintype "bidirectional"))
    )
    (net (code "58") (name "Net-(IC4-R)") (class "Default")
      (node (ref "IC4") (pin "2") (pinfunction "R_2") (pintype "bidirectional"))
      (node (ref "U$1") (pin "28") (pinfunction "28_28") (pintype "bidirectional"))
    )
    (net (code "59") (name "Net-(IC4-Y)") (class "Default")
      (node (ref "IC4") (pin "5") (pinfunction "Y_5") (pintype "bidirectional"))
      (node (ref "SERIAL2") (pin "1") (pinfunction "1_1") (pintype "bidirectional"))
    )
    (net (code "60") (name "Net-(IC4-Z)") (class "Default")
      (node (ref "IC4") (pin "6") (pinfunction "Z_6") (pintype "bidirectional"))
      (node (ref "SERIAL2") (pin "2") (pinfunction "2_2") (pintype "bidirectional"))
    )
    (net (code "61") (name "Net-(IC5-A)") (class "Default")
      (node (ref "IC5") (pin "8") (pinfunction "A_8") (pintype "bidirectional"))
      (node (ref "R12") (pin "2") (pinfunction "2_2") (pintype "passive"))
      (node (ref "SERIAL1") (pin "4") (pinfunction "4_4") (pintype "bidirectional"))
    )
    (net (code "62") (name "Net-(IC5-B)") (class "Default")
      (node (ref "IC5") (pin "7") (pinfunction "B_7") (pintype "bidirectional"))
      (node (ref "R12") (pin "1") (pinfunction "1_1") (pintype "passive"))
      (node (ref "SERIAL1") (pin "3") (pinfunction "3_3") (pintype "bidirectional"))
    )
    (net (code "63") (name "Net-(IC5-D)") (class "Default")
      (node (ref "IC5") (pin "3") (pinfunction "D_3") (pintype "bidirectional"))
      (node (ref "U$1") (pin "35/A16") (pinfunction "35/A16/PWM_35/A16") (pintype "bidirectional"))
    )
    (net (code "64") (name "Net-(IC5-R)") (class "Default")
      (node (ref "IC5") (pin "2") (pinfunction "R_2") (pintype "bidirectional"))
      (node (ref "U$1") (pin "34/A15") (pinfunction "34/A15/RX5/CAN1-RX_34/A15") (pintype "bidirectional"))
    )
    (net (code "65") (name "Net-(IC5-Y)") (class "Default")
      (node (ref "IC5") (pin "5") (pinfunction "Y_5") (pintype "bidirectional"))
      (node (ref "SERIAL1") (pin "1") (pinfunction "1_1") (pintype "bidirectional"))
    )
    (net (code "66") (name "Net-(IC5-Z)") (class "Default")
      (node (ref "IC5") (pin "6") (pinfunction "Z_6") (pintype "bidirectional"))
      (node (ref "SERIAL1") (pin "2") (pinfunction "2_2") (pintype "bidirectional"))
    )
    (net (code "67") (name "Net-(IC6-A1)") (class "Default")
      (node (ref "IC6") (pin "1") (pinfunction "A1_1") (pintype "bidirectional"))
      (node (ref "R2") (pin "1") (pinfunction "1_1") (pintype "passive"))
    )
    (net (code "68") (name "Net-(IC6-A2)") (class "Default")
      (node (ref "IC6") (pin "3") (pinfunction "A2_3") (pintype "bidirectional"))
      (node (ref "U$4") (pin "GND") (pinfunction "GND_GND") (pintype "bidirectional"))
    )
    (net (code "69") (name "Net-(IC6-C1)") (class "Default")
      (node (ref "IC6") (pin "2") (pinfunction "C1_2") (pintype "bidirectional"))
      (node (ref "U$3") (pin "GND") (pinfunction "GND_GND") (pintype "bidirectional"))
    )
    (net (code "70") (name "Net-(IC6-C2)") (class "Default")
      (node (ref "IC6") (pin "4") (pinfunction "C2_4") (pintype "bidirectional"))
      (node (ref "R3") (pin "1") (pinfunction "1_1") (pintype "passive"))
    )
    (net (code "71") (name "Net-(IC7-VISO)") (class "Default")
      (node (ref "C17") (pin "2") (pinfunction "2_2") (pintype "passive"))
      (node (ref "C7") (pin "2") (pinfunction "2_2") (pintype "passive"))
      (node (ref "IC7") (pin "11") (pinfunction "VSEL_11") (pintype "passive"))
      (node (ref "IC7") (pin "16") (pinfunction "VISO_16") (pintype "passive"))
    )
    (net (code "72") (name "Net-(IC7-VOA)") (class "Default")
      (node (ref "C16") (pin "1") (pinfunction "1_1") (pintype "passive"))
      (node (ref "IC7") (pin "14") (pinfunction "VOA_14") (pintype "passive"))
      (node (ref "U$5") (pin "S") (pinfunction "OUT_S") (pintype "bidirectional"))
    )
    (net (code "73") (name "Net-(IC7-VOB)") (class "Default")
      (node (ref "C18") (pin "1") (pinfunction "1_1") (pintype "passive"))
      (node (ref "IC7") (pin "13") (pinfunction "VOB_13") (pintype "passive"))
      (node (ref "U$2") (pin "S") (pinfunction "OUT_S") (pintype "bidirectional"))
    )
    (net (code "74") (name "Net-(IC10-PadVOUT+)") (class "Default")
      (node (ref "IC10") (pin "VOUT+") (pinfunction "VOUT+_VOUT+") (pintype "bidirectional"))
      (node (ref "IC14") (pin "+VOUT") (pinfunction "+VOUT_+VOUT") (pintype "bidirectional"))
      (node (ref "L2") (pin "1") (pinfunction "1_1") (pintype "passive"))
    )
    (net (code "75") (name "Net-(IC11-PadVOUT+)") (class "Default")
      (node (ref "IC11") (pin "VOUT+") (pinfunction "VOUT+_VOUT+") (pintype "bidirectional"))
      (node (ref "IC15") (pin "+VOUT") (pinfunction "+VOUT_+VOUT") (pintype "bidirectional"))
      (node (ref "L3") (pin "1") (pinfunction "1_1") (pintype "passive"))
    )
    (net (code "76") (name "Net-(IC12-2IN)") (class "Default")
      (node (ref "IC12") (pin "5") (pinfunction "2IN_5") (pintype "bidirectional"))
      (node (ref "PORT1") (pin "1") (pinfunction "1_1") (pintype "bidirectional"))
      (node (ref "R4") (pin "1") (pinfunction "1_1") (pintype "passive"))
    )
    (net (code "77") (name "Net-(IC12-3IN)") (class "Default")
      (node (ref "IC12") (pin "7") (pinfunction "3IN_7") (pintype "bidirectional"))
      (node (ref "PORT2") (pin "1") (pinfunction "1_1") (pintype "bidirectional"))
      (node (ref "R5") (pin "1") (pinfunction "1_1") (pintype "passive"))
    )
    (net (code "78") (name "Net-(IC12-4IN)") (class "Default")
      (node (ref "IC12") (pin "9") (pinfunction "4IN_9") (pintype "bidirectional"))
      (node (ref "PORT3") (pin "1") (pinfunction "1_1") (pintype "bidirectional"))
      (node (ref "R6") (pin "2") (pinfunction "2_2") (pintype "passive"))
    )
    (net (code "79") (name "Net-(IC12-5IN)") (class "Default")
      (node (ref "IC12") (pin "11") (pinfunction "5IN_11") (pintype "bidirectional"))
      (node (ref "PORT4") (pin "1") (pinfunction "1_1") (pintype "bidirectional"))
      (node (ref "R7") (pin "2") (pinfunction "2_2") (pintype "passive"))
    )
    (net (code "80") (name "Net-(IC13-Pad+VOUT)") (class "Default")
      (node (ref "IC13") (pin "+VOUT") (pinfunction "+VOUT_+VOUT") (pintype "bidirectional"))
      (node (ref "IC9") (pin "VOUT+") (pinfunction "VOUT+_VOUT+") (pintype "bidirectional"))
      (node (ref "L1") (pin "1") (pinfunction "1_1") (pintype "passive"))
    )
    (net (code "81") (name "Net-(U$3-OUT)") (class "Default")
      (node (ref "R2") (pin "2") (pinfunction "2_2") (pintype "passive"))
      (node (ref "U$3") (pin "S") (pinfunction "OUT_S") (pintype "bidirectional"))
    )
    (net (code "82") (name "Net-(U$4-OUT)") (class "Default")
      (node (ref "R3") (pin "2") (pinfunction "2_2") (pintype "passive"))
      (node (ref "U$4") (pin "S") (pinfunction "OUT_S") (pintype "bidirectional"))
    )
    (net (code "83") (name "Net-(U$8-2)") (class "Default")
      (node (ref "R1") (pin "2") (pinfunction "2_2") (pintype "passive"))
      (node (ref "U$8") (pin "P$2") (pinfunction "2_P$2") (pintype "bidirectional"))
    )
    (net (code "84") (name "VCC") (class "Default")
      (node (ref "C1") (pin "1") (pinfunction "1_1") (pintype "passive"))
      (node (ref "C11") (pin "1") (pinfunction "1_1") (pintype "passive"))
      (node (ref "C12") (pin "2") (pinfunction "2_2") (pintype "passive"))
      (node (ref "C13") (pin "1") (pinfunction "1_1") (pintype "passive"))
      (node (ref "C2") (pin "1") (pinfunction "1_1") (pintype "passive"))
      (node (ref "C3") (pin "1") (pinfunction "1_1") (pintype "passive"))
      (node (ref "C4") (pin "1") (pinfunction "1_1") (pintype "passive"))
      (node (ref "C5") (pin "1") (pinfunction "1_1") (pintype "passive"))
      (node (ref "IC1") (pin "1") (pinfunction "VCC_1") (pintype "bidirectional"))
      (node (ref "IC12") (pin "1") (pinfunction "VCC_1") (pintype "bidirectional"))
      (node (ref "IC2") (pin "1") (pinfunction "VCC_1") (pintype "bidirectional"))
      (node (ref "IC3") (pin "1") (pinfunction "VCC_1") (pintype "bidirectional"))
      (node (ref "IC4") (pin "1") (pinfunction "VCC_1") (pintype "bidirectional"))
      (node (ref "IC5") (pin "1") (pinfunction "VCC_1") (pintype "bidirectional"))
      (node (ref "IC6") (pin "8") (pinfunction "CL1_8") (pintype "bidirectional"))
      (node (ref "IC8") (pin "P$2") (pinfunction "P$2_P$2") (pintype "bidirectional"))
      (node (ref "U$1") (pin "3.3V") (pinfunction "3.3V_3.3V") (pintype "power_in"))
      (node (ref "U$1") (pin "3.3V3") (pinfunction "3.3V_3.3V3") (pintype "power_in"))
    )
    (net (code "85") (name "unconnected-(IC7-NC-Pad12)") (class "Default")
      (node (ref "IC7") (pin "12") (pinfunction "NC_12") (pintype "passive"))
    )
    (net (code "86") (name "unconnected-(IC7-NC_2-Pad7)") (class "Default")
      (node (ref "IC7") (pin "7") (pinfunction "NC_2_7") (pintype "passive"))
    )
    (net (code "87") (name "unconnected-(IC7-RCSEL-Pad6)") (class "Default")
      (node (ref "IC7") (pin "6") (pinfunction "RCSEL_6") (pintype "passive"))
    )
    (net (code "88") (name "unconnected-(IC7-VE2-Pad10)") (class "Default")
      (node (ref "IC7") (pin "10") (pinfunction "VE2_10") (pintype "passive"))
    )
    (net (code "89") (name "unconnected-(IC8-PadP$1)") (class "Default")
      (node (ref "IC8") (pin "P$1") (pinfunction "P$1_P$1") (pintype "bidirectional"))
    )
    (net (code "90") (name "unconnected-(IC8-PadP$14)") (class "Default")
      (node (ref "IC8") (pin "P$14") (pinfunction "P$14_P$14") (pintype "bidirectional"))
    )
    (net (code "91") (name "unconnected-(IC8-PadP$16)") (class "Default")
      (node (ref "IC8") (pin "P$16") (pinfunction "P$16_P$16") (pintype "bidirectional"))
    )
    (net (code "92") (name "unconnected-(IC8-PadP$17)") (class "Default")
      (node (ref "IC8") (pin "P$17") (pinfunction "P$17_P$17") (pintype "bidirectional"))
    )
    (net (code "93") (name "unconnected-(IC8-PadP$18)") (class "Default")
      (node (ref "IC8") (pin "P$18") (pinfunction "P$18_P$18") (pintype "bidirectional"))
    )
    (net (code "94") (name "unconnected-(IC8-PadP$20)") (class "Default")
      (node (ref "IC8") (pin "P$20") (pinfunction "P$20_P$20") (pintype "bidirectional"))
    )
    (net (code "95") (name "unconnected-(IC12-1IN-Pad3)") (class "Default")
      (node (ref "IC12") (pin "3") (pinfunction "1IN_3") (pintype "bidirectional"))
    )
    (net (code "96") (name "unconnected-(IC12-1OUT-Pad2)") (class "Default")
      (node (ref "IC12") (pin "2") (pinfunction "1OUT_2") (pintype "bidirectional"))
    )
    (net (code "97") (name "unconnected-(IC12-6IN-Pad14)") (class "Default")
      (node (ref "IC12") (pin "14") (pinfunction "6IN_14") (pintype "bidirectional"))
    )
    (net (code "98") (name "unconnected-(IC12-6OUT-Pad15)") (class "Default")
      (node (ref "IC12") (pin "15") (pinfunction "6OUT_15") (pintype "bidirectional"))
    )
    (net (code "99") (name "unconnected-(IC12-NC-Pad16)") (class "Default")
      (node (ref "IC12") (pin "16") (pinfunction "NC_16") (pintype "bidirectional"))
    )
    (net (code "100") (name "unconnected-(IC12-NC2-Pad13)") (class "Default")
      (node (ref "IC12") (pin "13") (pinfunction "NC2_13") (pintype "bidirectional"))
    )
    (net (code "101") (name "unconnected-(IC13-PadNC)") (class "Default")
      (node (ref "IC13") (pin "NC") (pinfunction "NC_NC") (pintype "bidirectional"))
    )
    (net (code "102") (name "unconnected-(IC14-PadNC)") (class "Default")
      (node (ref "IC14") (pin "NC") (pinfunction "NC_NC") (pintype "bidirectional"))
    )
    (net (code "103") (name "unconnected-(IC15-PadNC)") (class "Default")
      (node (ref "IC15") (pin "NC") (pinfunction "NC_NC") (pintype "bidirectional"))
    )
    (net (code "104") (name "unconnected-(PORT1-Pad2)") (class "Default")
      (node (ref "PORT1") (pin "2") (pinfunction "2_2") (pintype "bidirectional"))
    )
    (net (code "105") (name "unconnected-(PORT1-Pad8)") (class "Default")
      (node (ref "PORT1") (pin "8") (pinfunction "8_8") (pintype "bidirectional"))
    )
    (net (code "106") (name "unconnected-(PORT2-Pad2)") (class "Default")
      (node (ref "PORT2") (pin "2") (pinfunction "2_2") (pintype "bidirectional"))
    )
    (net (code "107") (name "unconnected-(PORT2-Pad8)") (class "Default")
      (node (ref "PORT2") (pin "8") (pinfunction "8_8") (pintype "bidirectional"))
    )
    (net (code "108") (name "unconnected-(PORT3-Pad2)") (class "Default")
      (node (ref "PORT3") (pin "2") (pinfunction "2_2") (pintype "bidirectional"))
    )
    (net (code "109") (name "unconnected-(PORT3-Pad8)") (class "Default")
      (node (ref "PORT3") (pin "8") (pinfunction "8_8") (pintype "bidirectional"))
    )
    (net (code "110") (name "unconnected-(PORT4-Pad2)") (class "Default")
      (node (ref "PORT4") (pin "2") (pinfunction "2_2") (pintype "bidirectional"))
    )
    (net (code "111") (name "unconnected-(PORT4-Pad8)") (class "Default")
      (node (ref "PORT4") (pin "8") (pinfunction "8_8") (pintype "bidirectional"))
    )
    (net (code "112") (name "unconnected-(SERIAL1-Pad5)") (class "Default")
      (node (ref "SERIAL1") (pin "5") (pinfunction "5_5") (pintype "bidirectional"))
    )
    (net (code "113") (name "unconnected-(SERIAL1-Pad6)") (class "Default")
      (node (ref "SERIAL1") (pin "6") (pinfunction "6_6") (pintype "bidirectional"))
    )
    (net (code "114") (name "unconnected-(SERIAL1-Pad7)") (class "Default")
      (node (ref "SERIAL1") (pin "7") (pinfunction "7_7") (pintype "bidirectional"))
    )
    (net (code "115") (name "unconnected-(SERIAL1-Pad8)") (class "Default")
      (node (ref "SERIAL1") (pin "8") (pinfunction "8_8") (pintype "bidirectional"))
    )
    (net (code "116") (name "unconnected-(SERIAL2-Pad5)") (class "Default")
      (node (ref "SERIAL2") (pin "5") (pinfunction "5_5") (pintype "bidirectional"))
    )
    (net (code "117") (name "unconnected-(SERIAL2-Pad6)") (class "Default")
      (node (ref "SERIAL2") (pin "6") (pinfunction "6_6") (pintype "bidirectional"))
    )
    (net (code "118") (name "unconnected-(SERIAL2-Pad7)") (class "Default")
      (node (ref "SERIAL2") (pin "7") (pinfunction "7_7") (pintype "bidirectional"))
    )
    (net (code "119") (name "unconnected-(SERIAL2-Pad8)") (class "Default")
      (node (ref "SERIAL2") (pin "8") (pinfunction "8_8") (pintype "bidirectional"))
    )
    (net (code "120") (name "unconnected-(SERIAL3-Pad7)") (class "Default")
      (node (ref "SERIAL3") (pin "7") (pinfunction "7_7") (pintype "bidirectional"))
    )
    (net (code "121") (name "unconnected-(SERIAL3-Pad8)") (class "Default")
      (node (ref "SERIAL3") (pin "8") (pinfunction "8_8") (pintype "bidirectional"))
    )
    (net (code "122") (name "unconnected-(SERIAL4-Pad7)") (class "Default")
      (node (ref "SERIAL4") (pin "7") (pinfunction "7_7") (pintype "bidirectional"))
    )
    (net (code "123") (name "unconnected-(SERIAL4-Pad8)") (class "Default")
      (node (ref "SERIAL4") (pin "8") (pinfunction "8_8") (pintype "bidirectional"))
    )
    (net (code "124") (name "unconnected-(SERIAL5-Pad7)") (class "Default")
      (node (ref "SERIAL5") (pin "7") (pinfunction "7_7") (pintype "bidirectional"))
    )
    (net (code "125") (name "unconnected-(SERIAL5-Pad8)") (class "Default")
      (node (ref "SERIAL5") (pin "8") (pinfunction "8_8") (pintype "bidirectional"))
    )
    (net (code "126") (name "unconnected-(U$1-9{slash}RX2{slash}PWM-Pad9)") (class "Default")
      (node (ref "U$1") (pin "9") (pinfunction "9/RX2/PWM_9") (pintype "bidirectional"))
    )
    (net (code "127") (name "unconnected-(U$1-10{slash}TX2{slash}PWM-Pad10)") (class "Default")
      (node (ref "U$1") (pin "10") (pinfunction "10/TX2/PWM_10") (pintype "bidirectional"))
    )
    (net (code "128") (name "unconnected-(U$1-11{slash}MOSI0-Pad11)") (class "Default")
      (node (ref "U$1") (pin "11") (pinfunction "11/MOSI0_11") (pintype "bidirectional"))
    )
    (net (code "129") (name "unconnected-(U$1-12{slash}MISO0-Pad12)") (class "Default")
      (node (ref "U$1") (pin "12") (pinfunction "12/MISO0_12") (pintype "bidirectional"))
    )
    (net (code "130") (name "unconnected-(U$1-13{slash}SCK0{slash}LED-Pad13)") (class "Default")
      (node (ref "U$1") (pin "13") (pinfunction "13/SCK0/LED_13") (pintype "bidirectional"))
    )
    (net (code "131") (name "unconnected-(U$1-31{slash}A12{slash}RX4-Pad31{slash}A12)") (class "Default")
      (node (ref "U$1") (pin "31/A12") (pinfunction "31/A12/RX4_31/A12") (pintype "bidirectional"))
    )
    (net (code "132") (name "unconnected-(U$1-A21{slash}DAC0-PadA21)") (class "Default")
      (node (ref "U$1") (pin "A21") (pinfunction "A21/DAC0_A21") (pintype "bidirectional"))
    )
    (net (code "133") (name "unconnected-(U$1-A22{slash}DAC1-PadA22)") (class "Default")
      (node (ref "U$1") (pin "A22") (pinfunction "A22/DAC1_A22") (pintype "bidirectional"))
    )
    (net (code "134") (name "unconnected-(U$1-Pad26)") (class "Default")
      (node (ref "U$1") (pin "26") (pinfunction "26_26") (pintype "bidirectional"))
    )
    (net (code "135") (name "unconnected-(U$1-Pad27)") (class "Default")
      (node (ref "U$1") (pin "27") (pinfunction "27_27") (pintype "bidirectional"))
    )
  )
)
